# Adafruit_Qualia_Driver.net
KiCad netlist of a schematic drawn in EAGLE
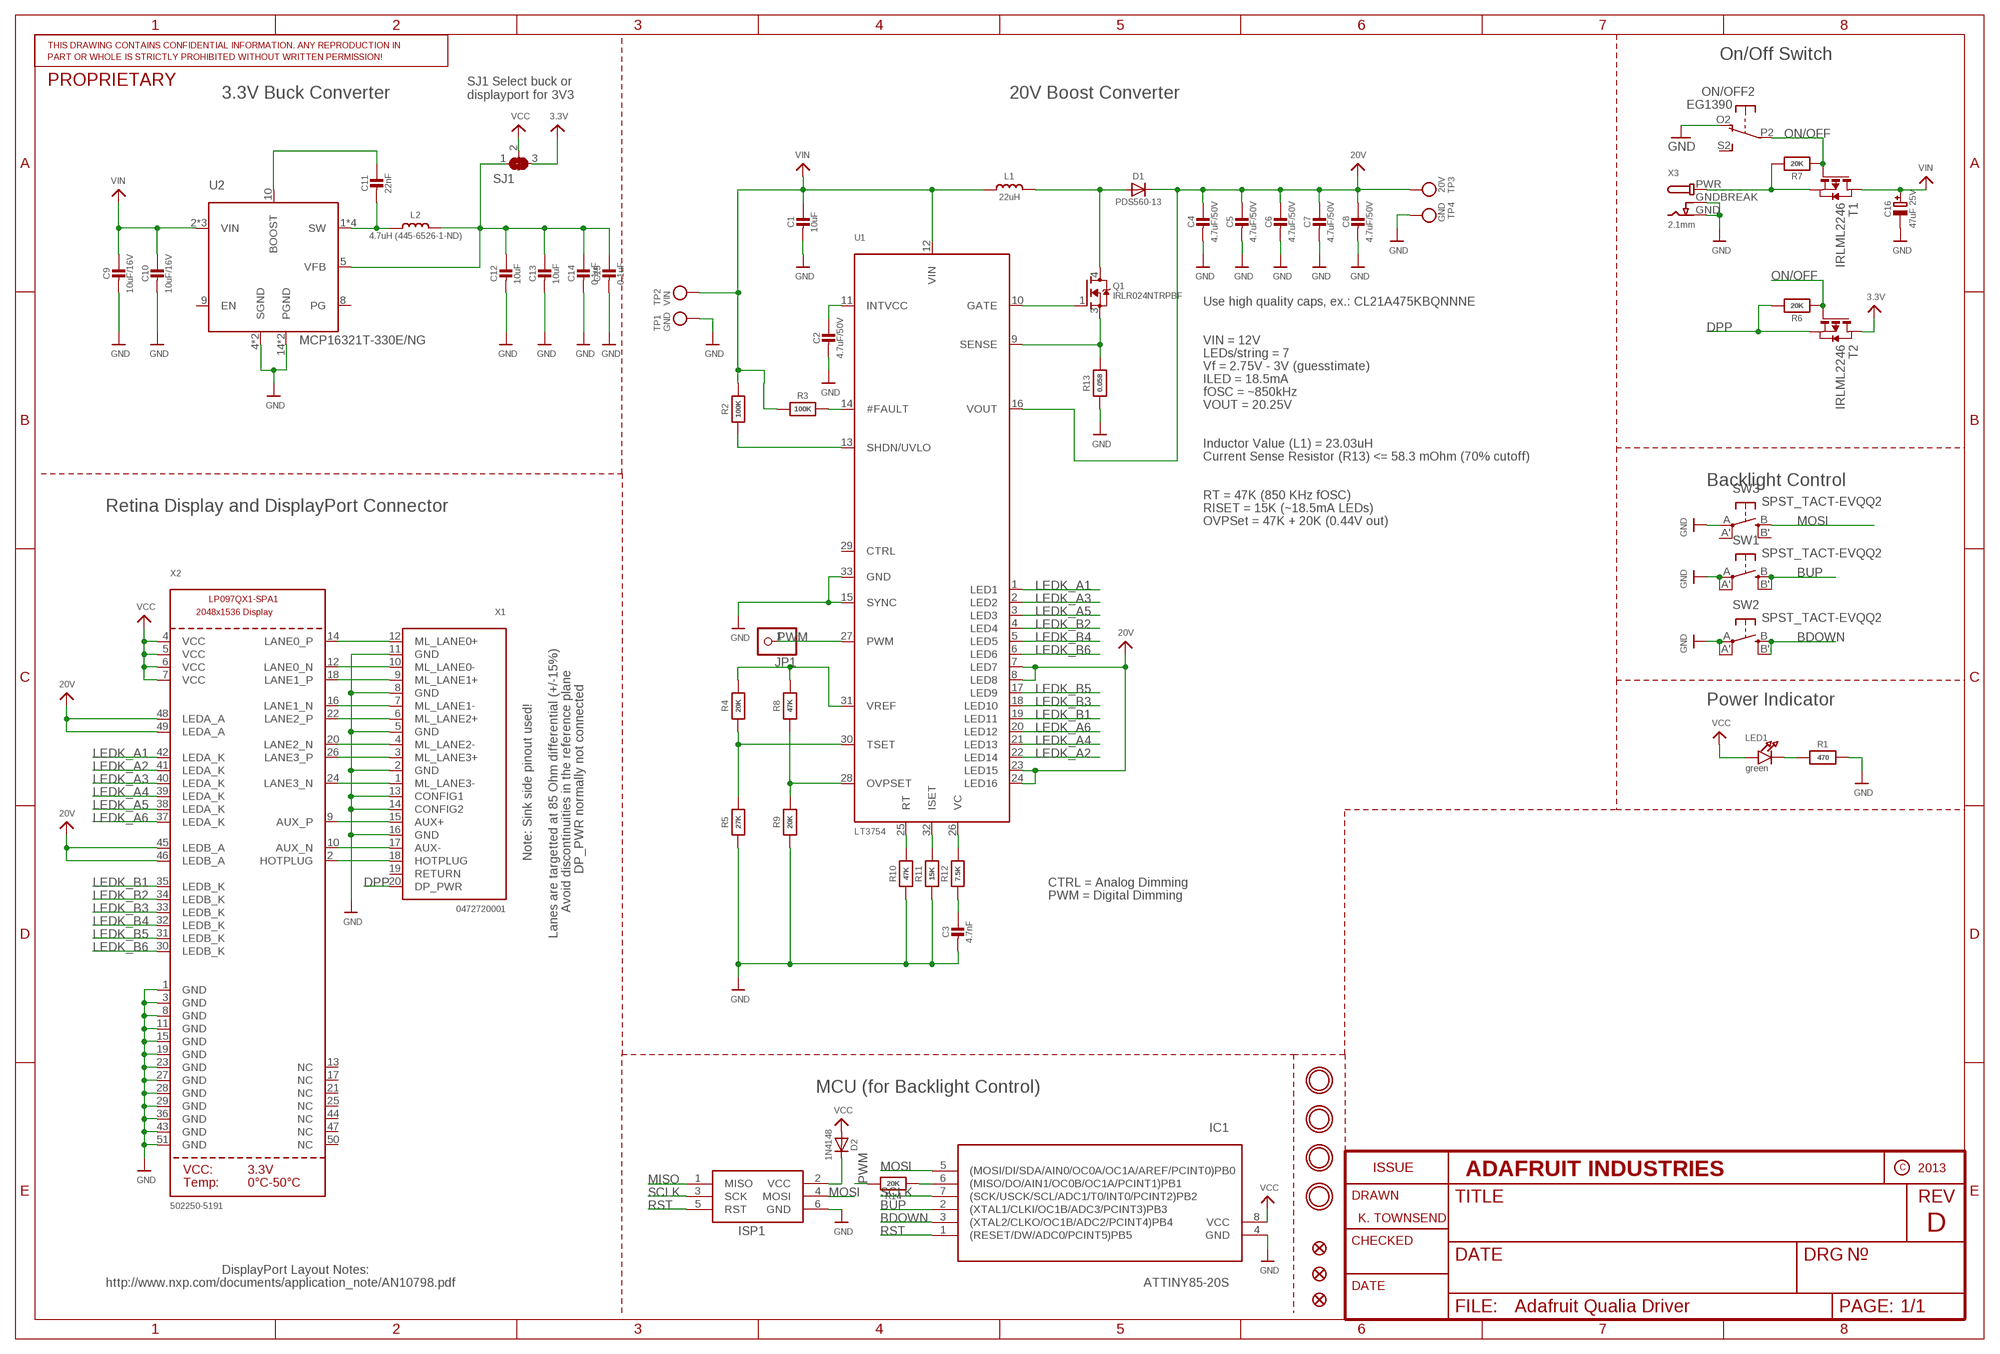
[diagram p0: schematic, sheet 1]

(export (version "E")
  (design (tool "Eeschema 10.0.6"))
  (components
    (comp (ref "C1")
      (value "10uF")
      (footprint "eagle-import:_0805")
      (libsource (lib "eagle-import") (part "CAP_CERAMIC_0805"))
    )
    (comp (ref "C2")
      (value "4.7uF/50V")
      (footprint "eagle-import:_0805")
      (libsource (lib "eagle-import") (part "CAP_CERAMIC_0805"))
    )
    (comp (ref "C3")
      (value "4.7nF")
      (footprint "eagle-import:_0805")
      (libsource (lib "eagle-import") (part "CAP_CERAMIC_0805"))
    )
    (comp (ref "C4")
      (value "4.7uF/50V")
      (footprint "eagle-import:_0805")
      (libsource (lib "eagle-import") (part "CAP_CERAMIC_0805"))
    )
    (comp (ref "C5")
      (value "4.7uF/50V")
      (footprint "eagle-import:_0805")
      (libsource (lib "eagle-import") (part "CAP_CERAMIC_0805"))
    )
    (comp (ref "C6")
      (value "4.7uF/50V")
      (footprint "eagle-import:_0805")
      (libsource (lib "eagle-import") (part "CAP_CERAMIC_0805"))
    )
    (comp (ref "C7")
      (value "4.7uF/50V")
      (footprint "eagle-import:_0805")
      (libsource (lib "eagle-import") (part "CAP_CERAMIC_0805"))
    )
    (comp (ref "C8")
      (value "4.7uF/50V")
      (footprint "eagle-import:_0805")
      (libsource (lib "eagle-import") (part "CAP_CERAMIC_0805"))
    )
    (comp (ref "C9")
      (value "10uF/16V")
      (footprint "eagle-import:_0805")
      (libsource (lib "eagle-import") (part "CAP_CERAMIC_0805"))
    )
    (comp (ref "C10")
      (value "10uF/16V")
      (footprint "eagle-import:_0805")
      (libsource (lib "eagle-import") (part "CAP_CERAMIC_0805"))
    )
    (comp (ref "C11")
      (value "22nF")
      (footprint "eagle-import:_0805")
      (libsource (lib "eagle-import") (part "CAP_CERAMIC_0805"))
    )
    (comp (ref "C12")
      (value "10uF")
      (footprint "eagle-import:_0805")
      (libsource (lib "eagle-import") (part "CAP_CERAMIC_0805"))
    )
    (comp (ref "C13")
      (value "10uF")
      (footprint "eagle-import:_0805")
      (libsource (lib "eagle-import") (part "CAP_CERAMIC_0805"))
    )
    (comp (ref "C14")
      (value "0.1uF")
      (footprint "eagle-import:_0805")
      (libsource (lib "eagle-import") (part "CAP_CERAMIC_0805"))
    )
    (comp (ref "C15")
      (value "0.1uF")
      (footprint "eagle-import:_0805")
      (libsource (lib "eagle-import") (part "CAP_CERAMIC_0805"))
    )
    (comp (ref "C16")
      (value "47uF 25V")
      (footprint "eagle-import:PANASONIC_C")
      (libsource (lib "eagle-import") (part "CAP_ELECTROLYTICPANASONIC_C"))
    )
    (comp (ref "D1")
      (value "PDS560-13")
      (footprint "eagle-import:POWERDI-5")
      (libsource (lib "eagle-import") (part "DIODEPOWERDI"))
    )
    (comp (ref "D2")
      (value "1N4148")
      (footprint "eagle-import:SOD-323")
      (libsource (lib "eagle-import") (part "DIODESOD-323"))
    )
    (comp (ref "FID1")
      (value "FIDUCIAL\"\"")
      (footprint "eagle-import:FIDUCIAL_1MM")
      (libsource (lib "eagle-import") (part "FIDUCIAL{dblquote}{dblquote}"))
    )
    (comp (ref "FID2")
      (value "FIDUCIAL\"\"")
      (footprint "eagle-import:FIDUCIAL_1MM")
      (libsource (lib "eagle-import") (part "FIDUCIAL{dblquote}{dblquote}"))
    )
    (comp (ref "FID3")
      (value "FIDUCIAL\"\"")
      (footprint "eagle-import:FIDUCIAL_1MM")
      (libsource (lib "eagle-import") (part "FIDUCIAL{dblquote}{dblquote}"))
    )
    (comp (ref "IC1")
      (value "ATTINY85-20S")
      (footprint "eagle-import:SOIC8")
      (libsource (lib "eagle-import") (part "ATTINY85S-20"))
    )
    (comp (ref "ISP1")
      (value "AVRISP-6")
      (footprint "eagle-import:AVRISP")
      (libsource (lib "eagle-import") (part "AVRISP-6"))
    )
    (comp (ref "JP1")
      (value "PINHD-1X1CB")
      (footprint "eagle-import:1X01-CLEANBIG")
      (libsource (lib "eagle-import") (part "PINHD-1X1CB"))
    )
    (comp (ref "L1")
      (value "22uH")
      (footprint "eagle-import:INDUCTOR_6X6MM_SUMIDA_CDRH5D28")
      (libsource (lib "eagle-import") (part "INDUCTORCDRH5D28"))
    )
    (comp (ref "L2")
      (value "4.7uH (445-6526-1-ND)")
      (footprint "eagle-import:INDUCTOR_5X5MM_TDK_VLC5045")
      (libsource (lib "eagle-import") (part "INDUCTORTDK_VLC5045"))
    )
    (comp (ref "LED1")
      (value "green")
      (footprint "eagle-import:CHIPLED_0805")
      (libsource (lib "eagle-import") (part "LED0805"))
    )
    (comp (ref "ON/OFF")
      (value "EG1390")
      (footprint "eagle-import:EG1390")
      (libsource (lib "eagle-import") (part "DPDT-EG1390"))
    )
    (comp (ref "Q1")
      (value "IRLR024NTRPBF")
      (footprint "eagle-import:DPAK")
      (libsource (lib "eagle-import") (part "MOSFET-NDPAK"))
    )
    (comp (ref "R1")
      (value "470")
      (footprint "eagle-import:_0805")
      (libsource (lib "eagle-import") (part "RESISTOR_0805"))
    )
    (comp (ref "R2")
      (value "100K")
      (footprint "eagle-import:_0805")
      (libsource (lib "eagle-import") (part "RESISTOR_0805"))
    )
    (comp (ref "R3")
      (value "100K")
      (footprint "eagle-import:_0805")
      (libsource (lib "eagle-import") (part "RESISTOR_0805"))
    )
    (comp (ref "R4")
      (value "20K")
      (footprint "eagle-import:_0805")
      (libsource (lib "eagle-import") (part "RESISTOR_0805"))
    )
    (comp (ref "R5")
      (value "27K")
      (footprint "eagle-import:_0805")
      (libsource (lib "eagle-import") (part "RESISTOR_0805"))
    )
    (comp (ref "R6")
      (value "20K")
      (footprint "eagle-import:_0805MP")
      (libsource (lib "eagle-import") (part "RESISTOR_0805MP"))
    )
    (comp (ref "R7")
      (value "20K")
      (footprint "eagle-import:_0805MP")
      (libsource (lib "eagle-import") (part "RESISTOR_0805MP"))
    )
    (comp (ref "R8")
      (value "47K")
      (footprint "eagle-import:_0805")
      (libsource (lib "eagle-import") (part "RESISTOR_0805"))
    )
    (comp (ref "R9")
      (value "20K")
      (footprint "eagle-import:_0805")
      (libsource (lib "eagle-import") (part "RESISTOR_0805"))
    )
    (comp (ref "R10")
      (value "47K")
      (footprint "eagle-import:_0805")
      (libsource (lib "eagle-import") (part "RESISTOR_0805"))
    )
    (comp (ref "R11")
      (value "15K")
      (footprint "eagle-import:_0805")
      (libsource (lib "eagle-import") (part "RESISTOR_0805"))
    )
    (comp (ref "R12")
      (value "7.5K")
      (footprint "eagle-import:_0805")
      (libsource (lib "eagle-import") (part "RESISTOR_0805"))
    )
    (comp (ref "R13")
      (value "0.058")
      (footprint "eagle-import:2512")
      (libsource (lib "eagle-import") (part "RESISTOR2512"))
    )
    (comp (ref "R14")
      (value "20K")
      (footprint "eagle-import:_0805")
      (libsource (lib "eagle-import") (part "RESISTOR_0805"))
    )
    (comp (ref "SJ1")
      (value "SOLDERJUMPER_2WAY")
      (footprint "eagle-import:SOLDERJUMPER_2WAY_OPEN_NOPASTE")
      (libsource (lib "eagle-import") (part "SOLDERJUMPER_2WAY"))
    )
    (comp (ref "SW1")
      (value "SPST_TACT-EVQQ2")
      (footprint "eagle-import:EVQ-Q2")
      (libsource (lib "eagle-import") (part "SPST_TACT-EVQQ2"))
    )
    (comp (ref "SW2")
      (value "SPST_TACT-EVQQ2")
      (footprint "eagle-import:EVQ-Q2")
      (libsource (lib "eagle-import") (part "SPST_TACT-EVQQ2"))
    )
    (comp (ref "SW3")
      (value "SPST_TACT-EVQQ2")
      (footprint "eagle-import:EVQ-Q2")
      (libsource (lib "eagle-import") (part "SPST_TACT-EVQQ2"))
    )
    (comp (ref "T1")
      (value "IRLML2246")
      (footprint "eagle-import:SOT-23")
      (libsource (lib "eagle-import") (part "PMOSSOT23"))
    )
    (comp (ref "T2")
      (value "IRLML2246")
      (footprint "eagle-import:SOT-23")
      (libsource (lib "eagle-import") (part "PMOSSOT23"))
    )
    (comp (ref "TP1")
      (value "GND")
      (footprint "eagle-import:TESTPOINT_ROUND_1MM")
      (libsource (lib "eagle-import") (part "TESTPOINTROUND1MM"))
    )
    (comp (ref "TP2")
      (value "VIN")
      (footprint "eagle-import:TESTPOINT_ROUND_1MM")
      (libsource (lib "eagle-import") (part "TESTPOINTROUND1MM"))
    )
    (comp (ref "TP3")
      (value "20V")
      (footprint "eagle-import:TESTPOINT_ROUND_1MM")
      (libsource (lib "eagle-import") (part "TESTPOINTROUND1MM"))
    )
    (comp (ref "TP4")
      (value "GND")
      (footprint "eagle-import:TESTPOINT_ROUND_1MM")
      (libsource (lib "eagle-import") (part "TESTPOINTROUND1MM"))
    )
    (comp (ref "U$11")
      (value "MOUNTINGHOLE3.0THIN")
      (footprint "eagle-import:MOUNTINGHOLE_3.0_PLATEDTHIN")
      (libsource (lib "eagle-import") (part "MOUNTINGHOLE3.0THIN"))
    )
    (comp (ref "U$32")
      (value "MOUNTINGHOLE3.0THIN")
      (footprint "eagle-import:MOUNTINGHOLE_3.0_PLATEDTHIN")
      (libsource (lib "eagle-import") (part "MOUNTINGHOLE3.0THIN"))
    )
    (comp (ref "U$33")
      (value "MOUNTINGHOLE3.0THIN")
      (footprint "eagle-import:MOUNTINGHOLE_3.0_PLATEDTHIN")
      (libsource (lib "eagle-import") (part "MOUNTINGHOLE3.0THIN"))
    )
    (comp (ref "U$34")
      (value "MOUNTINGHOLE3.0THIN")
      (footprint "eagle-import:MOUNTINGHOLE_3.0_PLATEDTHIN")
      (libsource (lib "eagle-import") (part "MOUNTINGHOLE3.0THIN"))
    )
    (comp (ref "U1")
      (value "LT3754")
      (footprint "eagle-import:QFN32_5MM")
      (libsource (lib "eagle-import") (part "VREG_LT3754"))
    )
    (comp (ref "U2")
      (value "MCP16321T-330E/NG")
      (footprint "eagle-import:QFN16_3MM")
      (libsource (lib "eagle-import") (part "VREG_MCP16321/2"))
    )
    (comp (ref "X1")
      (value "0472720001")
      (footprint "eagle-import:DISPLAYPORT_0472720001")
      (libsource (lib "eagle-import") (part "DISPLAYPORTSINKSIDE"))
    )
    (comp (ref "X2")
      (value "502250-5191")
      (footprint "eagle-import:FPC_51PIN_502250-5191_EXT")
      (libsource (lib "eagle-import") (part "DISP_DISPLAYPORT_LP097QX1-SPA1HANDSOLDERING"))
    )
    (comp (ref "X3")
      (value "2.1mm")
      (footprint "eagle-import:DCJACK_2MM_SMT")
      (libsource (lib "eagle-import") (part "DCBARRELSMT_CORRECT"))
    )
  )
  (nets
    (net (code "1") (name "/BDOWN") (class "Default")
      (node (ref "IC1") (pin "3") (pinfunction "(XTAL2/CLKO/OC1B/ADC2/PCINT4)PB4_3") (pintype "bidirectional"))
      (node (ref "SW2") (pin "B") (pinfunction "S_B") (pintype "passive"))
      (node (ref "SW2") (pin "B'") (pinfunction "S1_B'") (pintype "passive"))
    )
    (net (code "2") (name "/BUP") (class "Default")
      (node (ref "IC1") (pin "2") (pinfunction "(XTAL1/CLKI/OC1B/ADC3/PCINT3)PB3_2") (pintype "bidirectional"))
      (node (ref "SW1") (pin "B") (pinfunction "S_B") (pintype "passive"))
      (node (ref "SW1") (pin "B'") (pinfunction "S1_B'") (pintype "passive"))
    )
    (net (code "3") (name "/DPP") (class "Default")
      (node (ref "R6") (pin "2") (pinfunction "2_2") (pintype "passive"))
      (node (ref "T2") (pin "2") (pinfunction "S_2") (pintype "passive"))
      (node (ref "X1") (pin "20") (pinfunction "DP_PWR_20") (pintype "bidirectional"))
    )
    (net (code "4") (name "/LEDK_A1") (class "Default")
      (node (ref "U1") (pin "1") (pinfunction "LED1_1") (pintype "bidirectional"))
      (node (ref "X2") (pin "42") (pinfunction "LEDA_K_42") (pintype "bidirectional"))
    )
    (net (code "5") (name "/LEDK_A2") (class "Default")
      (node (ref "U1") (pin "22") (pinfunction "LED14_22") (pintype "bidirectional"))
      (node (ref "X2") (pin "41") (pinfunction "LEDA_K_41") (pintype "bidirectional"))
    )
    (net (code "6") (name "/LEDK_A3") (class "Default")
      (node (ref "U1") (pin "2") (pinfunction "LED2_2") (pintype "bidirectional"))
      (node (ref "X2") (pin "40") (pinfunction "LEDA_K_40") (pintype "bidirectional"))
    )
    (net (code "7") (name "/LEDK_A4") (class "Default")
      (node (ref "U1") (pin "21") (pinfunction "LED13_21") (pintype "bidirectional"))
      (node (ref "X2") (pin "39") (pinfunction "LEDA_K_39") (pintype "bidirectional"))
    )
    (net (code "8") (name "/LEDK_A5") (class "Default")
      (node (ref "U1") (pin "3") (pinfunction "LED3_3") (pintype "bidirectional"))
      (node (ref "X2") (pin "38") (pinfunction "LEDA_K_38") (pintype "bidirectional"))
    )
    (net (code "9") (name "/LEDK_A6") (class "Default")
      (node (ref "U1") (pin "20") (pinfunction "LED12_20") (pintype "bidirectional"))
      (node (ref "X2") (pin "37") (pinfunction "LEDA_K_37") (pintype "bidirectional"))
    )
    (net (code "10") (name "/LEDK_B1") (class "Default")
      (node (ref "U1") (pin "19") (pinfunction "LED11_19") (pintype "bidirectional"))
      (node (ref "X2") (pin "35") (pinfunction "LEDB_K_35") (pintype "bidirectional"))
    )
    (net (code "11") (name "/LEDK_B2") (class "Default")
      (node (ref "U1") (pin "4") (pinfunction "LED4_4") (pintype "bidirectional"))
      (node (ref "X2") (pin "34") (pinfunction "LEDB_K_34") (pintype "bidirectional"))
    )
    (net (code "12") (name "/LEDK_B3") (class "Default")
      (node (ref "U1") (pin "18") (pinfunction "LED10_18") (pintype "bidirectional"))
      (node (ref "X2") (pin "33") (pinfunction "LEDB_K_33") (pintype "bidirectional"))
    )
    (net (code "13") (name "/LEDK_B4") (class "Default")
      (node (ref "U1") (pin "5") (pinfunction "LED5_5") (pintype "bidirectional"))
      (node (ref "X2") (pin "32") (pinfunction "LEDB_K_32") (pintype "bidirectional"))
    )
    (net (code "14") (name "/LEDK_B5") (class "Default")
      (node (ref "U1") (pin "17") (pinfunction "LED9_17") (pintype "bidirectional"))
      (node (ref "X2") (pin "31") (pinfunction "LEDB_K_31") (pintype "bidirectional"))
    )
    (net (code "15") (name "/LEDK_B6") (class "Default")
      (node (ref "U1") (pin "6") (pinfunction "LED6_6") (pintype "bidirectional"))
      (node (ref "X2") (pin "30") (pinfunction "LEDB_K_30") (pintype "bidirectional"))
    )
    (net (code "16") (name "/MISO") (class "Default")
      (node (ref "IC1") (pin "6") (pinfunction "(MISO/DO/AIN1/OC0B/OC1A/PCINT1)PB1_6") (pintype "bidirectional"))
      (node (ref "ISP1") (pin "1") (pinfunction "MISO_1") (pintype "input"))
      (node (ref "R14") (pin "1") (pinfunction "1_1") (pintype "passive"))
    )
    (net (code "17") (name "/MOSI") (class "Default")
      (node (ref "IC1") (pin "5") (pinfunction "(MOSI/DI/SDA/AIN0/OC0A/OC1A/AREF/PCINT0)PB0_5") (pintype "bidirectional"))
      (node (ref "ISP1") (pin "4") (pinfunction "MOSI_4") (pintype "output"))
      (node (ref "SW3") (pin "B") (pinfunction "S_B") (pintype "passive"))
    )
    (net (code "18") (name "/ON{slash}OFF") (class "Default")
      (node (ref "ON/OFF") (pin "P2") (pinfunction "P_P2") (pintype "passive"))
      (node (ref "R6") (pin "1") (pinfunction "1_1") (pintype "passive"))
      (node (ref "R7") (pin "1") (pinfunction "1_1") (pintype "passive"))
      (node (ref "T1") (pin "3") (pinfunction "G_3") (pintype "passive"))
      (node (ref "T2") (pin "3") (pinfunction "G_3") (pintype "passive"))
    )
    (net (code "19") (name "/PWM") (class "Default")
      (node (ref "JP1") (pin "1") (pinfunction "1_1") (pintype "passive"))
      (node (ref "R14") (pin "2") (pinfunction "2_2") (pintype "passive"))
      (node (ref "U1") (pin "27") (pinfunction "PWM_27") (pintype "bidirectional"))
    )
    (net (code "20") (name "/RST") (class "Default")
      (node (ref "IC1") (pin "1") (pinfunction "(RESET/DW/ADC0/PCINT5)PB5_1") (pintype "bidirectional"))
      (node (ref "ISP1") (pin "5") (pinfunction "RST_5") (pintype "output"))
    )
    (net (code "21") (name "/SCLK") (class "Default")
      (node (ref "IC1") (pin "7") (pinfunction "(SCK/USCK/SCL/ADC1/T0/INT0/PCINT2)PB2_7") (pintype "bidirectional"))
      (node (ref "ISP1") (pin "3") (pinfunction "SCK_3") (pintype "output"))
    )
    (net (code "22") (name "3.3V") (class "Default")
      (node (ref "SJ1") (pin "3") (pinfunction "3_3") (pintype "passive"))
      (node (ref "T2") (pin "1") (pinfunction "D_1") (pintype "passive"))
    )
    (net (code "23") (name "20V") (class "Default")
      (node (ref "C4") (pin "1") (pinfunction "1_1") (pintype "passive"))
      (node (ref "C5") (pin "1") (pinfunction "1_1") (pintype "passive"))
      (node (ref "C6") (pin "1") (pinfunction "1_1") (pintype "passive"))
      (node (ref "C7") (pin "1") (pinfunction "1_1") (pintype "passive"))
      (node (ref "C8") (pin "1") (pinfunction "1_1") (pintype "passive"))
      (node (ref "D1") (pin "C") (pinfunction "C_C") (pintype "passive"))
      (node (ref "TP3") (pin "P$1") (pinfunction "P$1_P$1") (pintype "bidirectional"))
      (node (ref "U1") (pin "16") (pinfunction "VOUT_16") (pintype "bidirectional"))
      (node (ref "U1") (pin "23") (pinfunction "LED15_23") (pintype "bidirectional"))
      (node (ref "U1") (pin "24") (pinfunction "LED16_24") (pintype "bidirectional"))
      (node (ref "U1") (pin "7") (pinfunction "LED7_7") (pintype "bidirectional"))
      (node (ref "U1") (pin "8") (pinfunction "LED8_8") (pintype "bidirectional"))
      (node (ref "X2") (pin "45") (pinfunction "LEDB_A_45") (pintype "bidirectional"))
      (node (ref "X2") (pin "46") (pinfunction "LEDB_A_46") (pintype "bidirectional"))
      (node (ref "X2") (pin "48") (pinfunction "LEDA_A_48") (pintype "bidirectional"))
      (node (ref "X2") (pin "49") (pinfunction "LEDA_A_49") (pintype "bidirectional"))
    )
    (net (code "24") (name "GND") (class "Default")
      (node (ref "C1") (pin "2") (pinfunction "2_2") (pintype "passive"))
      (node (ref "C10") (pin "2") (pinfunction "2_2") (pintype "passive"))
      (node (ref "C12") (pin "2") (pinfunction "2_2") (pintype "passive"))
      (node (ref "C13") (pin "2") (pinfunction "2_2") (pintype "passive"))
      (node (ref "C14") (pin "2") (pinfunction "2_2") (pintype "passive"))
      (node (ref "C15") (pin "2") (pinfunction "2_2") (pintype "passive"))
      (node (ref "C16") (pin "-") (pinfunction "-_-") (pintype "passive"))
      (node (ref "C2") (pin "2") (pinfunction "2_2") (pintype "passive"))
      (node (ref "C3") (pin "2") (pinfunction "2_2") (pintype "passive"))
      (node (ref "C4") (pin "2") (pinfunction "2_2") (pintype "passive"))
      (node (ref "C5") (pin "2") (pinfunction "2_2") (pintype "passive"))
      (node (ref "C6") (pin "2") (pinfunction "2_2") (pintype "passive"))
      (node (ref "C7") (pin "2") (pinfunction "2_2") (pintype "passive"))
      (node (ref "C8") (pin "2") (pinfunction "2_2") (pintype "passive"))
      (node (ref "C9") (pin "2") (pinfunction "2_2") (pintype "passive"))
      (node (ref "IC1") (pin "4") (pinfunction "GND_4") (pintype "bidirectional"))
      (node (ref "ISP1") (pin "6") (pinfunction "GND_6") (pintype "power_in"))
      (node (ref "ON/OFF") (pin "O2") (pinfunction "O_O2") (pintype "passive"))
      (node (ref "R1") (pin "2") (pinfunction "2_2") (pintype "passive"))
      (node (ref "R10") (pin "1") (pinfunction "1_1") (pintype "passive"))
      (node (ref "R11") (pin "1") (pinfunction "1_1") (pintype "passive"))
      (node (ref "R13") (pin "1") (pinfunction "1_1") (pintype "passive"))
      (node (ref "R5") (pin "1") (pinfunction "1_1") (pintype "passive"))
      (node (ref "R9") (pin "1") (pinfunction "1_1") (pintype "passive"))
      (node (ref "SW1") (pin "A") (pinfunction "P_A") (pintype "passive"))
      (node (ref "SW1") (pin "A'") (pinfunction "P1_A'") (pintype "passive"))
      (node (ref "SW2") (pin "A") (pinfunction "P_A") (pintype "passive"))
      (node (ref "SW2") (pin "A'") (pinfunction "P1_A'") (pintype "passive"))
      (node (ref "SW3") (pin "A") (pinfunction "P_A") (pintype "passive"))
      (node (ref "TP1") (pin "P$1") (pinfunction "P$1_P$1") (pintype "bidirectional"))
      (node (ref "TP4") (pin "P$1") (pinfunction "P$1_P$1") (pintype "bidirectional"))
      (node (ref "U1") (pin "15") (pinfunction "SYNC_15") (pintype "bidirectional"))
      (node (ref "U1") (pin "33") (pinfunction "GND_33") (pintype "bidirectional"))
      (node (ref "U2") (pin "14") (pinfunction "PGND_14") (pintype "bidirectional"))
      (node (ref "U2") (pin "15") (pinfunction "PGND_15") (pintype "bidirectional"))
      (node (ref "U2") (pin "4") (pinfunction "SGND_4") (pintype "bidirectional"))
      (node (ref "U2") (pin "THERMAL") (pinfunction "SGND_THERMAL") (pintype "bidirectional"))
      (node (ref "X1") (pin "11") (pinfunction "GND_11") (pintype "bidirectional"))
      (node (ref "X1") (pin "13") (pinfunction "CONFIG1_13") (pintype "bidirectional"))
      (node (ref "X1") (pin "14") (pinfunction "CONFIG2_14") (pintype "bidirectional"))
      (node (ref "X1") (pin "16") (pinfunction "GND_16") (pintype "bidirectional"))
      (node (ref "X1") (pin "2") (pinfunction "GND_2") (pintype "bidirectional"))
      (node (ref "X1") (pin "5") (pinfunction "GND_5") (pintype "bidirectional"))
      (node (ref "X1") (pin "8") (pinfunction "GND_8") (pintype "bidirectional"))
      (node (ref "X2") (pin "1") (pinfunction "GND_1") (pintype "power_in"))
      (node (ref "X2") (pin "11") (pinfunction "GND_11") (pintype "power_in"))
      (node (ref "X2") (pin "15") (pinfunction "GND_15") (pintype "power_in"))
      (node (ref "X2") (pin "19") (pinfunction "GND_19") (pintype "power_in"))
      (node (ref "X2") (pin "23") (pinfunction "GND_23") (pintype "power_in"))
      (node (ref "X2") (pin "27") (pinfunction "GND_27") (pintype "power_in"))
      (node (ref "X2") (pin "28") (pinfunction "GND_28") (pintype "power_in"))
      (node (ref "X2") (pin "29") (pinfunction "GND_29") (pintype "power_in"))
      (node (ref "X2") (pin "3") (pinfunction "GND_3") (pintype "power_in"))
      (node (ref "X2") (pin "36") (pinfunction "GND_36") (pintype "power_in"))
      (node (ref "X2") (pin "43") (pinfunction "GND_43") (pintype "power_in"))
      (node (ref "X2") (pin "51") (pinfunction "GND_51") (pintype "power_in"))
      (node (ref "X2") (pin "8") (pinfunction "GND_8") (pintype "power_in"))
      (node (ref "X3") (pin "GND") (pinfunction "GND_GND") (pintype "power_in"))
      (node (ref "X3") (pin "GNDBREAK") (pinfunction "GNDBREAK_GNDBREAK") (pintype "power_in"))
    )
    (net (code "25") (name "Net-(C3-Pad1)") (class "Default")
      (node (ref "C3") (pin "1") (pinfunction "1_1") (pintype "passive"))
      (node (ref "R12") (pin "1") (pinfunction "1_1") (pintype "passive"))
    )
    (net (code "26") (name "Net-(ISP1-VCC)") (class "Default")
      (node (ref "D2") (pin "C") (pinfunction "C_C") (pintype "passive"))
      (node (ref "ISP1") (pin "2") (pinfunction "VCC_2") (pintype "power_in"))
    )
    (net (code "27") (name "Net-(L1-2)") (class "Default")
      (node (ref "D1") (pin "A1") (pinfunction "A_A1") (pintype "passive"))
      (node (ref "D1") (pin "A2") (pinfunction "A_A2") (pintype "passive"))
      (node (ref "L1") (pin "P$2") (pinfunction "2_P$2") (pintype "passive"))
      (node (ref "Q1") (pin "4") (pinfunction "D_4") (pintype "bidirectional"))
    )
    (net (code "28") (name "Net-(L2-1)") (class "Default")
      (node (ref "C11") (pin "2") (pinfunction "2_2") (pintype "passive"))
      (node (ref "L2") (pin "P$1") (pinfunction "1_P$1") (pintype "passive"))
      (node (ref "U2") (pin "1") (pinfunction "SW_1") (pintype "bidirectional"))
      (node (ref "U2") (pin "12") (pinfunction "SW_12") (pintype "bidirectional"))
      (node (ref "U2") (pin "13") (pinfunction "SW_13") (pintype "bidirectional"))
      (node (ref "U2") (pin "16") (pinfunction "SW_16") (pintype "bidirectional"))
    )
    (net (code "29") (name "Net-(L2-2)") (class "Default")
      (node (ref "C12") (pin "1") (pinfunction "1_1") (pintype "passive"))
      (node (ref "C13") (pin "1") (pinfunction "1_1") (pintype "passive"))
      (node (ref "C14") (pin "1") (pinfunction "1_1") (pintype "passive"))
      (node (ref "C15") (pin "1") (pinfunction "1_1") (pintype "passive"))
      (node (ref "L2") (pin "P$2") (pinfunction "2_P$2") (pintype "passive"))
      (node (ref "SJ1") (pin "1") (pinfunction "1_1") (pintype "passive"))
      (node (ref "U2") (pin "5") (pinfunction "VFB_5") (pintype "bidirectional"))
    )
    (net (code "30") (name "Net-(LED1-PadC)") (class "Default")
      (node (ref "LED1") (pin "C") (pinfunction "C_C") (pintype "passive"))
      (node (ref "R1") (pin "1") (pinfunction "1_1") (pintype "passive"))
    )
    (net (code "31") (name "Net-(Q1-G)") (class "Default")
      (node (ref "Q1") (pin "1") (pinfunction "G_1") (pintype "bidirectional"))
      (node (ref "U1") (pin "10") (pinfunction "GATE_10") (pintype "bidirectional"))
    )
    (net (code "32") (name "Net-(Q1-S)") (class "Default")
      (node (ref "Q1") (pin "3") (pinfunction "S_3") (pintype "bidirectional"))
      (node (ref "R13") (pin "2") (pinfunction "2_2") (pintype "passive"))
      (node (ref "U1") (pin "9") (pinfunction "SENSE_9") (pintype "bidirectional"))
    )
    (net (code "33") (name "Net-(T1-S)") (class "Default")
      (node (ref "R7") (pin "2") (pinfunction "2_2") (pintype "passive"))
      (node (ref "T1") (pin "2") (pinfunction "S_2") (pintype "passive"))
      (node (ref "X3") (pin "PWR") (pinfunction "PWR_PWR") (pintype "power_in"))
    )
    (net (code "34") (name "Net-(U1-#FAULT)") (class "Default")
      (node (ref "R3") (pin "2") (pinfunction "2_2") (pintype "passive"))
      (node (ref "U1") (pin "14") (pinfunction "#FAULT_14") (pintype "bidirectional"))
    )
    (net (code "35") (name "Net-(U1-INTVCC)") (class "Default")
      (node (ref "C2") (pin "1") (pinfunction "1_1") (pintype "passive"))
      (node (ref "U1") (pin "11") (pinfunction "INTVCC_11") (pintype "bidirectional"))
    )
    (net (code "36") (name "Net-(U1-ISET)") (class "Default")
      (node (ref "R11") (pin "2") (pinfunction "2_2") (pintype "passive"))
      (node (ref "U1") (pin "32") (pinfunction "ISET_32") (pintype "bidirectional"))
    )
    (net (code "37") (name "Net-(U1-OVPSET)") (class "Default")
      (node (ref "R8") (pin "1") (pinfunction "1_1") (pintype "passive"))
      (node (ref "R9") (pin "2") (pinfunction "2_2") (pintype "passive"))
      (node (ref "U1") (pin "28") (pinfunction "OVPSET_28") (pintype "bidirectional"))
    )
    (net (code "38") (name "Net-(U1-RT)") (class "Default")
      (node (ref "R10") (pin "2") (pinfunction "2_2") (pintype "passive"))
      (node (ref "U1") (pin "25") (pinfunction "RT_25") (pintype "bidirectional"))
    )
    (net (code "39") (name "Net-(U1-SHDN{slash}UVLO)") (class "Default")
      (node (ref "R2") (pin "1") (pinfunction "1_1") (pintype "passive"))
      (node (ref "U1") (pin "13") (pinfunction "SHDN/UVLO_13") (pintype "bidirectional"))
    )
    (net (code "40") (name "Net-(U1-TSET)") (class "Default")
      (node (ref "R4") (pin "1") (pinfunction "1_1") (pintype "passive"))
      (node (ref "R5") (pin "2") (pinfunction "2_2") (pintype "passive"))
      (node (ref "U1") (pin "30") (pinfunction "TSET_30") (pintype "bidirectional"))
    )
    (net (code "41") (name "Net-(U1-VC)") (class "Default")
      (node (ref "R12") (pin "2") (pinfunction "2_2") (pintype "passive"))
      (node (ref "U1") (pin "26") (pinfunction "VC_26") (pintype "bidirectional"))
    )
    (net (code "42") (name "Net-(U1-VREF)") (class "Default")
      (node (ref "R4") (pin "2") (pinfunction "2_2") (pintype "passive"))
      (node (ref "R8") (pin "2") (pinfunction "2_2") (pintype "passive"))
      (node (ref "U1") (pin "31") (pinfunction "VREF_31") (pintype "bidirectional"))
    )
    (net (code "43") (name "Net-(U2-BOOST)") (class "Default")
      (node (ref "C11") (pin "1") (pinfunction "1_1") (pintype "passive"))
      (node (ref "U2") (pin "10") (pinfunction "BOOST_10") (pintype "bidirectional"))
    )
    (net (code "44") (name "Net-(X1-AUX+)") (class "Default")
      (node (ref "X1") (pin "15") (pinfunction "AUX+_15") (pintype "bidirectional"))
      (node (ref "X2") (pin "9") (pinfunction "AUX_P_9") (pintype "bidirectional"))
    )
    (net (code "45") (name "Net-(X1-AUX-)") (class "Default")
      (node (ref "X1") (pin "17") (pinfunction "AUX-_17") (pintype "bidirectional"))
      (node (ref "X2") (pin "10") (pinfunction "AUX_N_10") (pintype "bidirectional"))
    )
    (net (code "46") (name "Net-(X1-HOTPLUG)") (class "Default")
      (node (ref "X1") (pin "18") (pinfunction "HOTPLUG_18") (pintype "bidirectional"))
      (node (ref "X2") (pin "2") (pinfunction "HOTPLUG_2") (pintype "bidirectional"))
    )
    (net (code "47") (name "Net-(X1-ML_LANE0+)") (class "Default")
      (node (ref "X1") (pin "12") (pinfunction "ML_LANE0+_12") (pintype "bidirectional"))
      (node (ref "X2") (pin "14") (pinfunction "LANE0_P_14") (pintype "bidirectional"))
    )
    (net (code "48") (name "Net-(X1-ML_LANE0-)") (class "Default")
      (node (ref "X1") (pin "10") (pinfunction "ML_LANE0-_10") (pintype "bidirectional"))
      (node (ref "X2") (pin "12") (pinfunction "LANE0_N_12") (pintype "bidirectional"))
    )
    (net (code "49") (name "Net-(X1-ML_LANE1+)") (class "Default")
      (node (ref "X1") (pin "9") (pinfunction "ML_LANE1+_9") (pintype "bidirectional"))
      (node (ref "X2") (pin "18") (pinfunction "LANE1_P_18") (pintype "bidirectional"))
    )
    (net (code "50") (name "Net-(X1-ML_LANE1-)") (class "Default")
      (node (ref "X1") (pin "7") (pinfunction "ML_LANE1-_7") (pintype "bidirectional"))
      (node (ref "X2") (pin "16") (pinfunction "LANE1_N_16") (pintype "bidirectional"))
    )
    (net (code "51") (name "Net-(X1-ML_LANE2+)") (class "Default")
      (node (ref "X1") (pin "6") (pinfunction "ML_LANE2+_6") (pintype "bidirectional"))
      (node (ref "X2") (pin "22") (pinfunction "LANE2_P_22") (pintype "bidirectional"))
    )
    (net (code "52") (name "Net-(X1-ML_LANE2-)") (class "Default")
      (node (ref "X1") (pin "4") (pinfunction "ML_LANE2-_4") (pintype "bidirectional"))
      (node (ref "X2") (pin "20") (pinfunction "LANE2_N_20") (pintype "bidirectional"))
    )
    (net (code "53") (name "Net-(X1-ML_LANE3+)") (class "Default")
      (node (ref "X1") (pin "3") (pinfunction "ML_LANE3+_3") (pintype "bidirectional"))
      (node (ref "X2") (pin "26") (pinfunction "LANE3_P_26") (pintype "bidirectional"))
    )
    (net (code "54") (name "Net-(X1-ML_LANE3-)") (class "Default")
      (node (ref "X1") (pin "1") (pinfunction "ML_LANE3-_1") (pintype "bidirectional"))
      (node (ref "X2") (pin "24") (pinfunction "LANE3_N_24") (pintype "bidirectional"))
    )
    (net (code "55") (name "VCC") (class "Default")
      (node (ref "D2") (pin "A") (pinfunction "A_A") (pintype "passive"))
      (node (ref "IC1") (pin "8") (pinfunction "VCC_8") (pintype "bidirectional"))
      (node (ref "LED1") (pin "A") (pinfunction "A_A") (pintype "passive"))
      (node (ref "SJ1") (pin "2") (pinfunction "2_2") (pintype "passive"))
      (node (ref "X2") (pin "4") (pinfunction "VCC_4") (pintype "power_in"))
      (node (ref "X2") (pin "5") (pinfunction "VCC_5") (pintype "power_in"))
      (node (ref "X2") (pin "6") (pinfunction "VCC_6") (pintype "power_in"))
      (node (ref "X2") (pin "7") (pinfunction "VCC_7") (pintype "power_in"))
    )
    (net (code "56") (name "VIN") (class "Default")
      (node (ref "C1") (pin "1") (pinfunction "1_1") (pintype "passive"))
      (node (ref "C10") (pin "1") (pinfunction "1_1") (pintype "passive"))
      (node (ref "C16") (pin "+") (pinfunction "+_+") (pintype "passive"))
      (node (ref "C9") (pin "1") (pinfunction "1_1") (pintype "passive"))
      (node (ref "L1") (pin "P$1") (pinfunction "1_P$1") (pintype "passive"))
      (node (ref "R2") (pin "2") (pinfunction "2_2") (pintype "passive"))
      (node (ref "R3") (pin "1") (pinfunction "1_1") (pintype "passive"))
      (node (ref "T1") (pin "1") (pinfunction "D_1") (pintype "passive"))
      (node (ref "TP2") (pin "P$1") (pinfunction "P$1_P$1") (pintype "bidirectional"))
      (node (ref "U1") (pin "12") (pinfunction "VIN_12") (pintype "bidirectional"))
      (node (ref "U2") (pin "11") (pinfunction "VIN_11") (pintype "bidirectional"))
      (node (ref "U2") (pin "2") (pinfunction "VIN_2") (pintype "bidirectional"))
      (node (ref "U2") (pin "3") (pinfunction "VIN_3") (pintype "bidirectional"))
    )
    (net (code "57") (name "unconnected-(ON/OFFB-S-PadS2)") (class "Default")
      (node (ref "ON/OFF") (pin "S2") (pinfunction "S_S2") (pintype "passive"))
    )
    (net (code "58") (name "unconnected-(SW3-P1-PadA')") (class "Default")
      (node (ref "SW3") (pin "A'") (pinfunction "P1_A'") (pintype "passive"))
    )
    (net (code "59") (name "unconnected-(SW3-S1-PadB')") (class "Default")
      (node (ref "SW3") (pin "B'") (pinfunction "S1_B'") (pintype "passive"))
    )
    (net (code "60") (name "unconnected-(U1-CTRL-Pad29)") (class "Default")
      (node (ref "U1") (pin "29") (pinfunction "CTRL_29") (pintype "bidirectional"))
    )
    (net (code "61") (name "unconnected-(U2-EN-Pad9)") (class "Default")
      (node (ref "U2") (pin "9") (pinfunction "EN_9") (pintype "bidirectional"))
    )
    (net (code "62") (name "unconnected-(U2-PG-Pad8)") (class "Default")
      (node (ref "U2") (pin "8") (pinfunction "PG_8") (pintype "bidirectional"))
    )
    (net (code "63") (name "unconnected-(X1-RETURN-Pad19)") (class "Default")
      (node (ref "X1") (pin "19") (pinfunction "RETURN_19") (pintype "bidirectional"))
    )
    (net (code "64") (name "unconnected-(X2-NC-Pad13)") (class "Default")
      (node (ref "X2") (pin "13") (pinfunction "NC_13") (pintype "no_connect"))
    )
    (net (code "65") (name "unconnected-(X2-NC-Pad17)") (class "Default")
      (node (ref "X2") (pin "17") (pinfunction "NC_17") (pintype "no_connect"))
    )
    (net (code "66") (name "unconnected-(X2-NC-Pad21)") (class "Default")
      (node (ref "X2") (pin "21") (pinfunction "NC_21") (pintype "no_connect"))
    )
    (net (code "67") (name "unconnected-(X2-NC-Pad25)") (class "Default")
      (node (ref "X2") (pin "25") (pinfunction "NC_25") (pintype "no_connect"))
    )
    (net (code "68") (name "unconnected-(X2-NC-Pad44)") (class "Default")
      (node (ref "X2") (pin "44") (pinfunction "NC_44") (pintype "no_connect"))
    )
    (net (code "69") (name "unconnected-(X2-NC-Pad47)") (class "Default")
      (node (ref "X2") (pin "47") (pinfunction "NC_47") (pintype "no_connect"))
    )
    (net (code "70") (name "unconnected-(X2-NC-Pad50)") (class "Default")
      (node (ref "X2") (pin "50") (pinfunction "NC_50") (pintype "no_connect"))
    )
  )
)
